# PIC_Schematic.net
KiCad netlist of a schematic drawn in Altium Designer
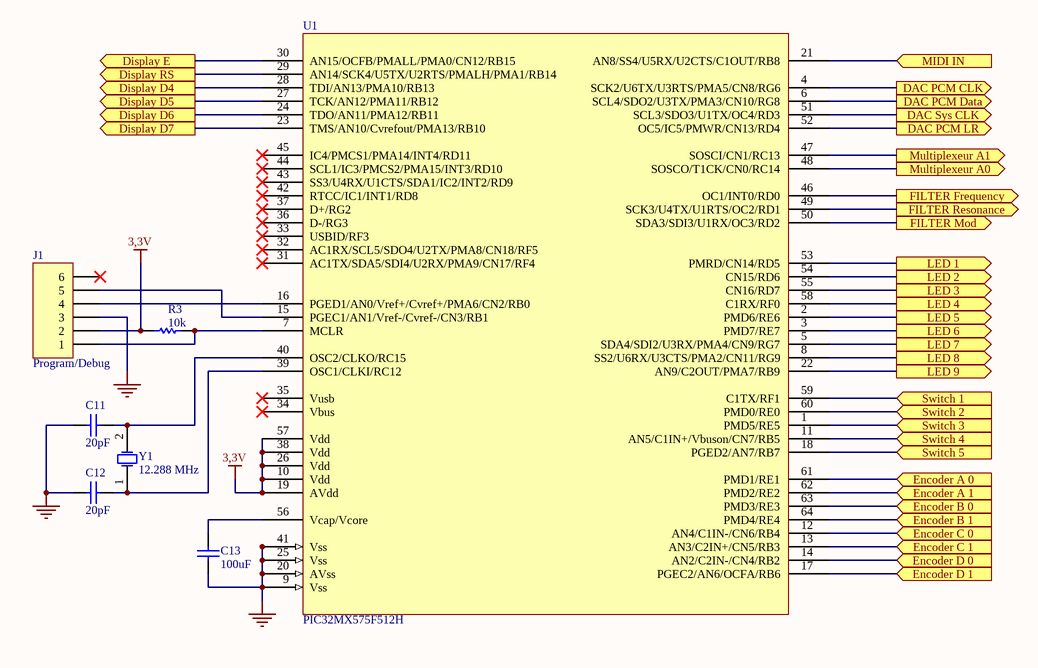
[diagram p0: PIC.Schematic.SchDoc]

(export (version "E")
  (design (tool "Eeschema 10.0.6"))
  (components
    (comp (ref "C11")
      (value "20pF")
      (footprint "CAP1608N")
      (description "Capacitor (Semiconductor SIM Model)")
      (fields (field (name "PUBLISHER") "Altium Limited"))
      (libsource (lib "Miscellaneous Devices") (part "Cap Semi"))
    )
    (comp (ref "C12")
      (value "20pF")
      (footprint "CAP1608N")
      (description "Capacitor (Semiconductor SIM Model)")
      (fields (field (name "PUBLISHER") "Altium Limited"))
      (libsource (lib "Miscellaneous Devices") (part "Cap Semi"))
    )
    (comp (ref "C13")
      (value "100uF")
      (footprint "RAD-0.3")
      (description "Capacitor")
      (fields (field (name "Comment") "Cap") (field (name "PUBLISHER") "Altium Limited"))
      (libsource (lib "Miscellaneous Devices") (part "Cap"))
    )
    (comp (ref "J1")
      (value "Program/Debug")
      (footprint "RJ11")
      (description "Header, 6-Pin, Right Angle")
      (fields (field (name "PUBLISHER") "Altium Limited"))
      (libsource (lib "Miscellaneous Connectors") (part "Header 6H"))
    )
    (comp (ref "R3")
      (value "10k")
      (footprint "CAPC1608N")
      (description "Resistor")
      (fields (field (name "PUBLISHER") "Altium Limited"))
      (libsource (lib "Miscellaneous Devices") (part "Res1"))
    )
    (comp (ref "U1")
      (value "PIC32MX575F512H")
      (footprint "PIC32")
      (libsource (lib "SynthyTwo.Components") (part "PIC32 MX575F512H"))
    )
    (comp (ref "Y1")
      (value "12.288 MHz")
      (footprint "HC49/4H SMX CRYSTAL")
      (description "Crystal Oscillator")
      (fields (field (name "PUBLISHER") "Altium Limited"))
      (libsource (lib "Miscellaneous Devices") (part "XTAL"))
    )
  )
  (nets
    (net (code "1") (name "/DAC PCM CLK") (class "Default")
      (node (ref "U1") (pin "4") (pinfunction "SCK2/U6TX/U3RTS/PMA5/CN8/RG6_4") (pintype "passive"))
    )
    (net (code "2") (name "/DAC PCM Data") (class "Default")
      (node (ref "U1") (pin "6") (pinfunction "SCL4/SDO2/U3TX/PMA3/CN10/RG8_6") (pintype "passive"))
    )
    (net (code "3") (name "/DAC PCM LR") (class "Default")
      (node (ref "U1") (pin "52") (pinfunction "OC5/IC5/PMWR/CN13/RD4_52") (pintype "passive"))
    )
    (net (code "4") (name "/DAC Sys CLK") (class "Default")
      (node (ref "U1") (pin "51") (pinfunction "SCL3/SDO3/U1TX/OC4/RD3_51") (pintype "passive"))
    )
    (net (code "5") (name "/Display D4") (class "Default")
      (node (ref "U1") (pin "28") (pinfunction "TDI/AN13/PMA10/RB13_28") (pintype "passive"))
    )
    (net (code "6") (name "/Display D5") (class "Default")
      (node (ref "U1") (pin "27") (pinfunction "TCK/AN12/PMA11/RB12_27") (pintype "passive"))
    )
    (net (code "7") (name "/Display D6") (class "Default")
      (node (ref "U1") (pin "24") (pinfunction "TDO/AN11/PMA12/RB11_24") (pintype "passive"))
    )
    (net (code "8") (name "/Display D7") (class "Default")
      (node (ref "U1") (pin "23") (pinfunction "TMS/AN10/Cvrefout/PMA13/RB10_23") (pintype "passive"))
    )
    (net (code "9") (name "/Display E") (class "Default")
      (node (ref "U1") (pin "30") (pinfunction "AN15/OCFB/PMALL/PMA0/CN12/RB15_30") (pintype "passive"))
    )
    (net (code "10") (name "/Display RS") (class "Default")
      (node (ref "U1") (pin "29") (pinfunction "AN14/SCK4/U5TX/U2RTS/PMALH/PMA1/RB14_29") (pintype "passive"))
    )
    (net (code "11") (name "/Encoder A 0") (class "Default")
      (node (ref "U1") (pin "61") (pinfunction "PMD1/RE1_61") (pintype "passive"))
    )
    (net (code "12") (name "/Encoder A 1") (class "Default")
      (node (ref "U1") (pin "62") (pinfunction "PMD2/RE2_62") (pintype "passive"))
    )
    (net (code "13") (name "/Encoder B 0") (class "Default")
      (node (ref "U1") (pin "63") (pinfunction "PMD3/RE3_63") (pintype "passive"))
    )
    (net (code "14") (name "/Encoder B 1") (class "Default")
      (node (ref "U1") (pin "64") (pinfunction "PMD4/RE4_64") (pintype "passive"))
    )
    (net (code "15") (name "/Encoder C 0") (class "Default")
      (node (ref "U1") (pin "12") (pinfunction "AN4/C1IN-/CN6/RB4_12") (pintype "passive"))
    )
    (net (code "16") (name "/Encoder C 1") (class "Default")
      (node (ref "U1") (pin "13") (pinfunction "AN3/C2IN+/CN5/RB3_13") (pintype "passive"))
    )
    (net (code "17") (name "/Encoder D 0") (class "Default")
      (node (ref "U1") (pin "14") (pinfunction "AN2/C2IN-/CN4/RB2_14") (pintype "passive"))
    )
    (net (code "18") (name "/Encoder D 1") (class "Default")
      (node (ref "U1") (pin "17") (pinfunction "PGEC2/AN6/OCFA/RB6_17") (pintype "passive"))
    )
    (net (code "19") (name "/FILTER Frequency") (class "Default")
      (node (ref "U1") (pin "46") (pinfunction "OC1/INT0/RD0_46") (pintype "passive"))
    )
    (net (code "20") (name "/FILTER Mod") (class "Default")
      (node (ref "U1") (pin "50") (pinfunction "SDA3/SDI3/U1RX/OC3/RD2_50") (pintype "passive"))
    )
    (net (code "21") (name "/FILTER Resonance") (class "Default")
      (node (ref "U1") (pin "49") (pinfunction "SCK3/U4TX/U1RTS/OC2/RD1_49") (pintype "passive"))
    )
    (net (code "22") (name "/LED 1") (class "Default")
      (node (ref "U1") (pin "53") (pinfunction "PMRD/CN14/RD5_53") (pintype "passive"))
    )
    (net (code "23") (name "/LED 2") (class "Default")
      (node (ref "U1") (pin "54") (pinfunction "CN15/RD6_54") (pintype "passive"))
    )
    (net (code "24") (name "/LED 3") (class "Default")
      (node (ref "U1") (pin "55") (pinfunction "CN16/RD7_55") (pintype "passive"))
    )
    (net (code "25") (name "/LED 4") (class "Default")
      (node (ref "U1") (pin "58") (pinfunction "C1RX/RF0_58") (pintype "passive"))
    )
    (net (code "26") (name "/LED 5") (class "Default")
      (node (ref "U1") (pin "2") (pinfunction "PMD6/RE6_2") (pintype "passive"))
    )
    (net (code "27") (name "/LED 6") (class "Default")
      (node (ref "U1") (pin "3") (pinfunction "PMD7/RE7_3") (pintype "passive"))
    )
    (net (code "28") (name "/LED 7") (class "Default")
      (node (ref "U1") (pin "5") (pinfunction "SDA4/SDI2/U3RX/PMA4/CN9/RG7_5") (pintype "passive"))
    )
    (net (code "29") (name "/LED 8") (class "Default")
      (node (ref "U1") (pin "8") (pinfunction "SS2/U6RX/U3CTS/PMA2/CN11/RG9_8") (pintype "passive"))
    )
    (net (code "30") (name "/LED 9") (class "Default")
      (node (ref "U1") (pin "22") (pinfunction "AN9/C2OUT/PMA7/RB9_22") (pintype "passive"))
    )
    (net (code "31") (name "/MIDI IN") (class "Default")
      (node (ref "U1") (pin "21") (pinfunction "AN8/SS4/U5RX/U2CTS/C1OUT/RB8_21") (pintype "passive"))
    )
    (net (code "32") (name "/Multiplexeur A0") (class "Default")
      (node (ref "U1") (pin "48") (pinfunction "SOSCO/T1CK/CN0/RC14_48") (pintype "passive"))
    )
    (net (code "33") (name "/Multiplexeur A1") (class "Default")
      (node (ref "U1") (pin "47") (pinfunction "SOSCI/CN1/RC13_47") (pintype "passive"))
    )
    (net (code "34") (name "/Switch 1") (class "Default")
      (node (ref "U1") (pin "59") (pinfunction "C1TX/RF1_59") (pintype "passive"))
    )
    (net (code "35") (name "/Switch 2") (class "Default")
      (node (ref "U1") (pin "60") (pinfunction "PMD0/RE0_60") (pintype "passive"))
    )
    (net (code "36") (name "/Switch 3") (class "Default")
      (node (ref "U1") (pin "1") (pinfunction "PMD5/RE5_1") (pintype "passive"))
    )
    (net (code "37") (name "/Switch 4") (class "Default")
      (node (ref "U1") (pin "11") (pinfunction "AN5/C1IN+/Vbuson/CN7/RB5_11") (pintype "passive"))
    )
    (net (code "38") (name "/Switch 5") (class "Default")
      (node (ref "U1") (pin "18") (pinfunction "PGED2/AN7/RB7_18") (pintype "passive"))
    )
    (net (code "39") (name "3,3V") (class "Default")
      (node (ref "J1") (pin "2") (pinfunction "2_2") (pintype "passive"))
      (node (ref "R3") (pin "2") (pinfunction "2_2") (pintype "passive"))
      (node (ref "U1") (pin "10") (pinfunction "Vdd_10") (pintype "passive"))
      (node (ref "U1") (pin "19") (pinfunction "AVdd_19") (pintype "passive"))
      (node (ref "U1") (pin "26") (pinfunction "Vdd_26") (pintype "passive"))
      (node (ref "U1") (pin "38") (pinfunction "Vdd_38") (pintype "passive"))
      (node (ref "U1") (pin "57") (pinfunction "Vdd_57") (pintype "passive"))
    )
    (net (code "40") (name "GND") (class "Default")
      (node (ref "C11") (pin "1") (pinfunction "1_1") (pintype "passive"))
      (node (ref "C12") (pin "1") (pinfunction "1_1") (pintype "passive"))
      (node (ref "C13") (pin "1") (pinfunction "1_1") (pintype "passive"))
      (node (ref "J1") (pin "3") (pinfunction "3_3") (pintype "passive"))
      (node (ref "U1") (pin "20") (pinfunction "AVss_20") (pintype "input"))
      (node (ref "U1") (pin "25") (pinfunction "Vss_25") (pintype "input"))
      (node (ref "U1") (pin "41") (pinfunction "Vss_41") (pintype "input"))
      (node (ref "U1") (pin "9") (pinfunction "Vss_9") (pintype "input"))
    )
    (net (code "41") (name "Net-(U1-MCLR)") (class "Default")
      (node (ref "J1") (pin "1") (pinfunction "1_1") (pintype "passive"))
      (node (ref "R3") (pin "1") (pinfunction "1_1") (pintype "passive"))
      (node (ref "U1") (pin "7") (pinfunction "MCLR_7") (pintype "passive"))
    )
    (net (code "42") (name "Net-(U1-OSC1{slash}CLKI{slash}RC12)") (class "Default")
      (node (ref "C12") (pin "2") (pinfunction "2_2") (pintype "passive"))
      (node (ref "U1") (pin "39") (pinfunction "OSC1/CLKI/RC12_39") (pintype "passive"))
      (node (ref "Y1") (pin "1") (pinfunction "OSC1_1") (pintype "passive"))
    )
    (net (code "43") (name "Net-(U1-OSC2{slash}CLKO{slash}RC15)") (class "Default")
      (node (ref "C11") (pin "2") (pinfunction "2_2") (pintype "passive"))
      (node (ref "U1") (pin "40") (pinfunction "OSC2/CLKO/RC15_40") (pintype "passive"))
      (node (ref "Y1") (pin "2") (pinfunction "OSC2_2") (pintype "passive"))
    )
    (net (code "44") (name "Net-(U1-PGEC1{slash}AN1{slash}Vref-{slash}Cvref-{slash}CN3{slash}RB1)") (class "Default")
      (node (ref "J1") (pin "5") (pinfunction "5_5") (pintype "passive"))
      (node (ref "U1") (pin "15") (pinfunction "PGEC1/AN1/Vref-/Cvref-/CN3/RB1_15") (pintype "passive"))
    )
    (net (code "45") (name "Net-(U1-PGED1{slash}AN0{slash}Vref+{slash}Cvref+{slash}PMA6{slash}CN2{slash}RB0)") (class "Default")
      (node (ref "J1") (pin "4") (pinfunction "4_4") (pintype "passive"))
      (node (ref "U1") (pin "16") (pinfunction "PGED1/AN0/Vref+/Cvref+/PMA6/CN2/RB0_16") (pintype "passive"))
    )
    (net (code "46") (name "Net-(U1-Vcap{slash}Vcore)") (class "Default")
      (node (ref "C13") (pin "2") (pinfunction "2_2") (pintype "passive"))
      (node (ref "U1") (pin "56") (pinfunction "Vcap/Vcore_56") (pintype "passive"))
    )
    (net (code "47") (name "unconnected-(J1-Pad6)") (class "Default")
      (node (ref "J1") (pin "6") (pinfunction "6_6") (pintype "passive+no_connect"))
    )
    (net (code "48") (name "unconnected-(U1-AC1RX{slash}SCL5{slash}SDO4{slash}U2TX{slash}PMA8{slash}CN18{slash}RF5-Pad32)") (class "Default")
      (node (ref "U1") (pin "32") (pinfunction "AC1RX/SCL5/SDO4/U2TX/PMA8/CN18/RF5_32") (pintype "passive+no_connect"))
    )
    (net (code "49") (name "unconnected-(U1-AC1TX{slash}SDA5{slash}SDI4{slash}U2RX{slash}PMA9{slash}CN17{slash}RF4-Pad31)") (class "Default")
      (node (ref "U1") (pin "31") (pinfunction "AC1TX/SDA5/SDI4/U2RX/PMA9/CN17/RF4_31") (pintype "passive+no_connect"))
    )
    (net (code "50") (name "unconnected-(U1-D+{slash}RG2-Pad37)") (class "Default")
      (node (ref "U1") (pin "37") (pinfunction "D+/RG2_37") (pintype "passive+no_connect"))
    )
    (net (code "51") (name "unconnected-(U1-D-{slash}RG3-Pad36)") (class "Default")
      (node (ref "U1") (pin "36") (pinfunction "D-/RG3_36") (pintype "passive+no_connect"))
    )
    (net (code "52") (name "unconnected-(U1-IC4{slash}PMCS1{slash}PMA14{slash}INT4{slash}RD11-Pad45)") (class "Default")
      (node (ref "U1") (pin "45") (pinfunction "IC4/PMCS1/PMA14/INT4/RD11_45") (pintype "passive+no_connect"))
    )
    (net (code "53") (name "unconnected-(U1-RTCC{slash}IC1{slash}INT1{slash}RD8-Pad42)") (class "Default")
      (node (ref "U1") (pin "42") (pinfunction "RTCC/IC1/INT1/RD8_42") (pintype "passive+no_connect"))
    )
    (net (code "54") (name "unconnected-(U1-SCL1{slash}IC3{slash}PMCS2{slash}PMA15{slash}INT3{slash}RD10-Pad44)") (class "Default")
      (node (ref "U1") (pin "44") (pinfunction "SCL1/IC3/PMCS2/PMA15/INT3/RD10_44") (pintype "passive+no_connect"))
    )
    (net (code "55") (name "unconnected-(U1-SS3{slash}U4RX{slash}U1CTS{slash}SDA1{slash}IC2{slash}INT2{slash}RD9-Pad43)") (class "Default")
      (node (ref "U1") (pin "43") (pinfunction "SS3/U4RX/U1CTS/SDA1/IC2/INT2/RD9_43") (pintype "passive+no_connect"))
    )
    (net (code "56") (name "unconnected-(U1-USBID{slash}RF3-Pad33)") (class "Default")
      (node (ref "U1") (pin "33") (pinfunction "USBID/RF3_33") (pintype "passive+no_connect"))
    )
    (net (code "57") (name "unconnected-(U1-Vbus-Pad34)") (class "Default")
      (node (ref "U1") (pin "34") (pinfunction "Vbus_34") (pintype "passive+no_connect"))
    )
    (net (code "58") (name "unconnected-(U1-Vusb-Pad35)") (class "Default")
      (node (ref "U1") (pin "35") (pinfunction "Vusb_35") (pintype "passive+no_connect"))
    )
  )
)
